# wolf_rev_d.net
KiCad netlist of a schematic drawn in EAGLE
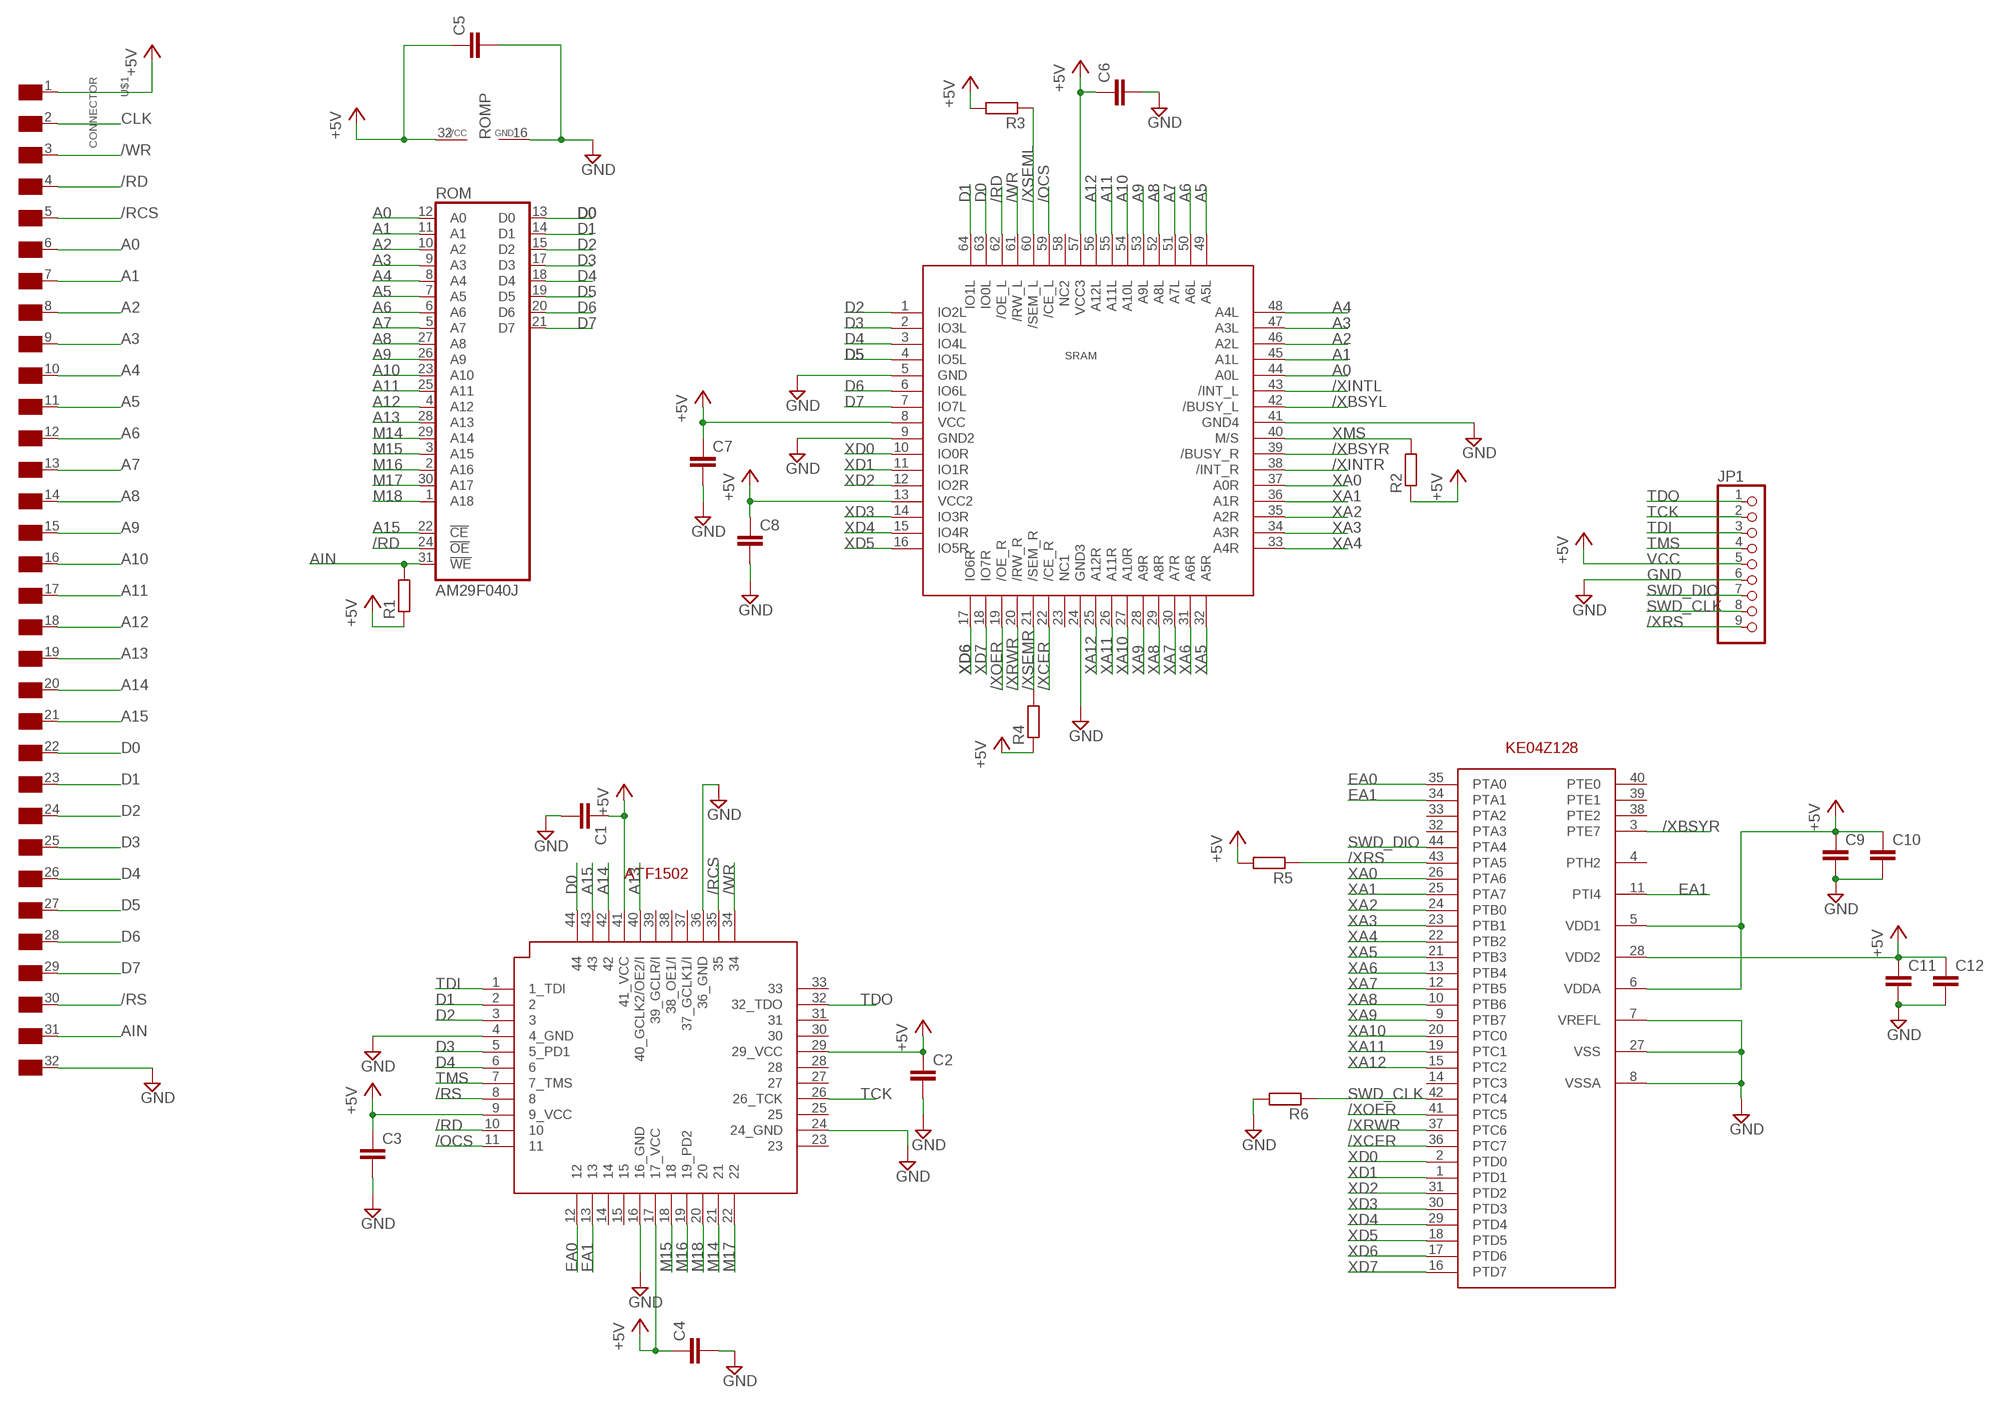
[diagram p0: schematic, sheet 1]

(export (version "E")
  (design (tool "Eeschema 10.0.6"))
  (components
    (comp (ref "ATF1502")
      (value "ATF1502")
      (footprint "eagle-import:TQFP44")
      (libsource (lib "eagle-import") (part "ATF1502"))
    )
    (comp (ref "C1")
      (value "C-EUC0805")
      (footprint "eagle-import:C0805")
      (libsource (lib "eagle-import") (part "C-EUC0805"))
    )
    (comp (ref "C2")
      (value "C-EUC0805")
      (footprint "eagle-import:C0805")
      (libsource (lib "eagle-import") (part "C-EUC0805"))
    )
    (comp (ref "C3")
      (value "C-EUC0805")
      (footprint "eagle-import:C0805")
      (libsource (lib "eagle-import") (part "C-EUC0805"))
    )
    (comp (ref "C4")
      (value "C-EUC0805")
      (footprint "eagle-import:C0805")
      (libsource (lib "eagle-import") (part "C-EUC0805"))
    )
    (comp (ref "C5")
      (value "C-EUC0805")
      (footprint "eagle-import:C0805")
      (libsource (lib "eagle-import") (part "C-EUC0805"))
    )
    (comp (ref "C6")
      (value "C-EUC0805")
      (footprint "eagle-import:C0805")
      (libsource (lib "eagle-import") (part "C-EUC0805"))
    )
    (comp (ref "C7")
      (value "C-EUC0805")
      (footprint "eagle-import:C0805")
      (libsource (lib "eagle-import") (part "C-EUC0805"))
    )
    (comp (ref "C8")
      (value "C-EUC0805")
      (footprint "eagle-import:C0805")
      (libsource (lib "eagle-import") (part "C-EUC0805"))
    )
    (comp (ref "C9")
      (value "C-EUC0805")
      (footprint "eagle-import:C0805")
      (libsource (lib "eagle-import") (part "C-EUC0805"))
    )
    (comp (ref "C10")
      (value "C-EUC0805")
      (footprint "eagle-import:C0805")
      (libsource (lib "eagle-import") (part "C-EUC0805"))
    )
    (comp (ref "C11")
      (value "C-EUC0805")
      (footprint "eagle-import:C0805")
      (libsource (lib "eagle-import") (part "C-EUC0805"))
    )
    (comp (ref "C12")
      (value "C-EUC0805")
      (footprint "eagle-import:C0805")
      (libsource (lib "eagle-import") (part "C-EUC0805"))
    )
    (comp (ref "JP1")
      (value "PINHD-1X9")
      (footprint "eagle-import:1X09")
      (libsource (lib "eagle-import") (part "PINHD-1X9"))
    )
    (comp (ref "KE04Z128")
      (value "KE04Z128")
      (footprint "eagle-import:TQFP44")
      (libsource (lib "eagle-import") (part "KE04Z128VLD4"))
    )
    (comp (ref "R1")
      (value "R-EU_R0805")
      (footprint "eagle-import:R0805")
      (libsource (lib "eagle-import") (part "R-EU_R0805"))
    )
    (comp (ref "R2")
      (value "R-EU_R0805")
      (footprint "eagle-import:R0805")
      (libsource (lib "eagle-import") (part "R-EU_R0805"))
    )
    (comp (ref "R3")
      (value "R-EU_R0805")
      (footprint "eagle-import:R0805")
      (libsource (lib "eagle-import") (part "R-EU_R0805"))
    )
    (comp (ref "R4")
      (value "R-EU_R0805")
      (footprint "eagle-import:R0805")
      (libsource (lib "eagle-import") (part "R-EU_R0805"))
    )
    (comp (ref "R5")
      (value "R-EU_R0805")
      (footprint "eagle-import:R0805")
      (libsource (lib "eagle-import") (part "R-EU_R0805"))
    )
    (comp (ref "R6")
      (value "R-EU_R0805")
      (footprint "eagle-import:R0805")
      (libsource (lib "eagle-import") (part "R-EU_R0805"))
    )
    (comp (ref "ROM")
      (value "AM29F040J")
      (footprint "eagle-import:PLCC32R")
      (libsource (lib "eagle-import") (part "AM29F040J"))
    )
    (comp (ref "SRAM")
      (value "CY7C144E")
      (footprint "eagle-import:TQFP64")
      (libsource (lib "eagle-import") (part "CY7C144E"))
    )
    (comp (ref "U$1")
      (value "CONNECTOR")
      (footprint "eagle-import:CONNECTOR")
      (libsource (lib "eagle-import") (part "CONNECTOR"))
    )
  )
  (nets
    (net (code "1") (name "+5V") (class "Default")
      (node (ref "ATF1502") (pin "17") (pinfunction "17_VCC_17") (pintype "bidirectional"))
      (node (ref "ATF1502") (pin "29") (pinfunction "29_VCC_29") (pintype "bidirectional"))
      (node (ref "ATF1502") (pin "41") (pinfunction "41_VCC_41") (pintype "bidirectional"))
      (node (ref "ATF1502") (pin "9") (pinfunction "9_VCC_9") (pintype "bidirectional"))
      (node (ref "C1") (pin "1") (pinfunction "1_1") (pintype "passive"))
      (node (ref "C10") (pin "1") (pinfunction "1_1") (pintype "passive"))
      (node (ref "C11") (pin "1") (pinfunction "1_1") (pintype "passive"))
      (node (ref "C12") (pin "1") (pinfunction "1_1") (pintype "passive"))
      (node (ref "C2") (pin "1") (pinfunction "1_1") (pintype "passive"))
      (node (ref "C3") (pin "1") (pinfunction "1_1") (pintype "passive"))
      (node (ref "C4") (pin "1") (pinfunction "1_1") (pintype "passive"))
      (node (ref "C5") (pin "1") (pinfunction "1_1") (pintype "passive"))
      (node (ref "C6") (pin "1") (pinfunction "1_1") (pintype "passive"))
      (node (ref "C7") (pin "1") (pinfunction "1_1") (pintype "passive"))
      (node (ref "C8") (pin "1") (pinfunction "1_1") (pintype "passive"))
      (node (ref "C9") (pin "1") (pinfunction "1_1") (pintype "passive"))
      (node (ref "JP1") (pin "5") (pinfunction "5_5") (pintype "passive"))
      (node (ref "KE04Z128") (pin "28") (pinfunction "VDD2_28") (pintype "bidirectional"))
      (node (ref "KE04Z128") (pin "5") (pinfunction "VDD1_5") (pintype "bidirectional"))
      (node (ref "KE04Z128") (pin "6") (pinfunction "VDDA_6") (pintype "bidirectional"))
      (node (ref "R1") (pin "1") (pinfunction "1_1") (pintype "passive"))
      (node (ref "R2") (pin "1") (pinfunction "1_1") (pintype "passive"))
      (node (ref "R3") (pin "2") (pinfunction "2_2") (pintype "passive"))
      (node (ref "R4") (pin "1") (pinfunction "1_1") (pintype "passive"))
      (node (ref "R5") (pin "2") (pinfunction "2_2") (pintype "passive"))
      (node (ref "ROM") (pin "32") (pinfunction "VCC_32") (pintype "power_in"))
      (node (ref "SRAM") (pin "13") (pinfunction "VCC2_13") (pintype "bidirectional"))
      (node (ref "SRAM") (pin "57") (pinfunction "VCC3_57") (pintype "bidirectional"))
      (node (ref "SRAM") (pin "8") (pinfunction "VCC_8") (pintype "bidirectional"))
      (node (ref "U$1") (pin "1") (pinfunction "VDD_1") (pintype "power_in"))
    )
    (net (code "2") (name "/A0") (class "Default")
      (node (ref "ROM") (pin "12") (pinfunction "A0_12") (pintype "input"))
      (node (ref "SRAM") (pin "44") (pinfunction "A0L_44") (pintype "bidirectional"))
      (node (ref "U$1") (pin "6") (pinfunction "A0_6") (pintype "bidirectional"))
    )
    (net (code "3") (name "/A1") (class "Default")
      (node (ref "ROM") (pin "11") (pinfunction "A1_11") (pintype "input"))
      (node (ref "SRAM") (pin "45") (pinfunction "A1L_45") (pintype "bidirectional"))
      (node (ref "U$1") (pin "7") (pinfunction "A1_7") (pintype "bidirectional"))
    )
    (net (code "4") (name "/A2") (class "Default")
      (node (ref "ROM") (pin "10") (pinfunction "A2_10") (pintype "input"))
      (node (ref "SRAM") (pin "46") (pinfunction "A2L_46") (pintype "bidirectional"))
      (node (ref "U$1") (pin "8") (pinfunction "A2_8") (pintype "bidirectional"))
    )
    (net (code "5") (name "/A3") (class "Default")
      (node (ref "ROM") (pin "9") (pinfunction "A3_9") (pintype "input"))
      (node (ref "SRAM") (pin "47") (pinfunction "A3L_47") (pintype "bidirectional"))
      (node (ref "U$1") (pin "9") (pinfunction "A3_9") (pintype "bidirectional"))
    )
    (net (code "6") (name "/A4") (class "Default")
      (node (ref "ROM") (pin "8") (pinfunction "A4_8") (pintype "input"))
      (node (ref "SRAM") (pin "48") (pinfunction "A4L_48") (pintype "bidirectional"))
      (node (ref "U$1") (pin "10") (pinfunction "A4_10") (pintype "bidirectional"))
    )
    (net (code "7") (name "/A5") (class "Default")
      (node (ref "ROM") (pin "7") (pinfunction "A5_7") (pintype "input"))
      (node (ref "SRAM") (pin "49") (pinfunction "A5L_49") (pintype "bidirectional"))
      (node (ref "U$1") (pin "11") (pinfunction "A5_11") (pintype "bidirectional"))
    )
    (net (code "8") (name "/A6") (class "Default")
      (node (ref "ROM") (pin "6") (pinfunction "A6_6") (pintype "input"))
      (node (ref "SRAM") (pin "50") (pinfunction "A6L_50") (pintype "bidirectional"))
      (node (ref "U$1") (pin "12") (pinfunction "A6_12") (pintype "bidirectional"))
    )
    (net (code "9") (name "/A7") (class "Default")
      (node (ref "ROM") (pin "5") (pinfunction "A7_5") (pintype "input"))
      (node (ref "SRAM") (pin "51") (pinfunction "A7L_51") (pintype "bidirectional"))
      (node (ref "U$1") (pin "13") (pinfunction "A7_13") (pintype "bidirectional"))
    )
    (net (code "10") (name "/A8") (class "Default")
      (node (ref "ROM") (pin "27") (pinfunction "A8_27") (pintype "input"))
      (node (ref "SRAM") (pin "52") (pinfunction "A8L_52") (pintype "bidirectional"))
      (node (ref "U$1") (pin "14") (pinfunction "A8_14") (pintype "bidirectional"))
    )
    (net (code "11") (name "/A9") (class "Default")
      (node (ref "ROM") (pin "26") (pinfunction "A9_26") (pintype "input"))
      (node (ref "SRAM") (pin "53") (pinfunction "A9L_53") (pintype "bidirectional"))
      (node (ref "U$1") (pin "15") (pinfunction "A9_15") (pintype "bidirectional"))
    )
    (net (code "12") (name "/A10") (class "Default")
      (node (ref "ROM") (pin "23") (pinfunction "A10_23") (pintype "input"))
      (node (ref "SRAM") (pin "54") (pinfunction "A10L_54") (pintype "bidirectional"))
      (node (ref "U$1") (pin "16") (pinfunction "A10_16") (pintype "bidirectional"))
    )
    (net (code "13") (name "/A11") (class "Default")
      (node (ref "ROM") (pin "25") (pinfunction "A11_25") (pintype "input"))
      (node (ref "SRAM") (pin "55") (pinfunction "A11L_55") (pintype "bidirectional"))
      (node (ref "U$1") (pin "17") (pinfunction "A11_17") (pintype "bidirectional"))
    )
    (net (code "14") (name "/A12") (class "Default")
      (node (ref "ROM") (pin "4") (pinfunction "A12_4") (pintype "input"))
      (node (ref "SRAM") (pin "56") (pinfunction "A12L_56") (pintype "bidirectional"))
      (node (ref "U$1") (pin "18") (pinfunction "A12_18") (pintype "bidirectional"))
    )
    (net (code "15") (name "/A13") (class "Default")
      (node (ref "ATF1502") (pin "40") (pinfunction "40_GCLK2/OE2/I_40") (pintype "bidirectional"))
      (node (ref "ROM") (pin "28") (pinfunction "A13_28") (pintype "input"))
      (node (ref "U$1") (pin "19") (pinfunction "A13_19") (pintype "bidirectional"))
    )
    (net (code "16") (name "/A14") (class "Default")
      (node (ref "ATF1502") (pin "42") (pinfunction "42_42") (pintype "bidirectional"))
      (node (ref "U$1") (pin "20") (pinfunction "A14_20") (pintype "bidirectional"))
    )
    (net (code "17") (name "/A15") (class "Default")
      (node (ref "ATF1502") (pin "43") (pinfunction "43_43") (pintype "bidirectional"))
      (node (ref "ROM") (pin "22") (pinfunction "~{CE}_22") (pintype "input"))
      (node (ref "U$1") (pin "21") (pinfunction "A15_21") (pintype "bidirectional"))
    )
    (net (code "18") (name "/AIN") (class "Default")
      (node (ref "R1") (pin "2") (pinfunction "2_2") (pintype "passive"))
      (node (ref "ROM") (pin "31") (pinfunction "~{WE}_31") (pintype "input"))
      (node (ref "U$1") (pin "31") (pinfunction "VIN_31") (pintype "bidirectional"))
    )
    (net (code "20") (name "/CLK") (class "Default")
      (node (ref "U$1") (pin "2") (pinfunction "NC_2") (pintype "no_connect"))
    )
    (net (code "21") (name "/D0") (class "Default")
      (node (ref "ATF1502") (pin "44") (pinfunction "44_44") (pintype "bidirectional"))
      (node (ref "ROM") (pin "13") (pinfunction "D0_13") (pintype "tri_state"))
      (node (ref "SRAM") (pin "63") (pinfunction "IO0L_63") (pintype "bidirectional"))
      (node (ref "U$1") (pin "22") (pinfunction "D0_22") (pintype "bidirectional"))
    )
    (net (code "22") (name "/D1") (class "Default")
      (node (ref "ATF1502") (pin "2") (pinfunction "2_2") (pintype "bidirectional"))
      (node (ref "ROM") (pin "14") (pinfunction "D1_14") (pintype "tri_state"))
      (node (ref "SRAM") (pin "64") (pinfunction "IO1L_64") (pintype "bidirectional"))
      (node (ref "U$1") (pin "23") (pinfunction "D1_23") (pintype "bidirectional"))
    )
    (net (code "23") (name "/D2") (class "Default")
      (node (ref "ATF1502") (pin "3") (pinfunction "3_3") (pintype "bidirectional"))
      (node (ref "ROM") (pin "15") (pinfunction "D2_15") (pintype "tri_state"))
      (node (ref "SRAM") (pin "1") (pinfunction "IO2L_1") (pintype "bidirectional"))
      (node (ref "U$1") (pin "24") (pinfunction "D2_24") (pintype "bidirectional"))
    )
    (net (code "24") (name "/D3") (class "Default")
      (node (ref "ATF1502") (pin "5") (pinfunction "5_PD1_5") (pintype "bidirectional"))
      (node (ref "ROM") (pin "17") (pinfunction "D3_17") (pintype "tri_state"))
      (node (ref "SRAM") (pin "2") (pinfunction "IO3L_2") (pintype "bidirectional"))
      (node (ref "U$1") (pin "25") (pinfunction "D3_25") (pintype "bidirectional"))
    )
    (net (code "25") (name "/D4") (class "Default")
      (node (ref "ATF1502") (pin "6") (pinfunction "6_6") (pintype "bidirectional"))
      (node (ref "ROM") (pin "18") (pinfunction "D4_18") (pintype "tri_state"))
      (node (ref "SRAM") (pin "3") (pinfunction "IO4L_3") (pintype "bidirectional"))
      (node (ref "U$1") (pin "26") (pinfunction "D4_26") (pintype "bidirectional"))
    )
    (net (code "26") (name "/D5") (class "Default")
      (node (ref "ROM") (pin "19") (pinfunction "D5_19") (pintype "tri_state"))
      (node (ref "SRAM") (pin "4") (pinfunction "IO5L_4") (pintype "bidirectional"))
      (node (ref "U$1") (pin "27") (pinfunction "D5_27") (pintype "bidirectional"))
    )
    (net (code "27") (name "/D6") (class "Default")
      (node (ref "ROM") (pin "20") (pinfunction "D6_20") (pintype "tri_state"))
      (node (ref "SRAM") (pin "6") (pinfunction "IO6L_6") (pintype "bidirectional"))
      (node (ref "U$1") (pin "28") (pinfunction "D6_28") (pintype "bidirectional"))
    )
    (net (code "28") (name "/D7") (class "Default")
      (node (ref "ROM") (pin "21") (pinfunction "D7_21") (pintype "tri_state"))
      (node (ref "SRAM") (pin "7") (pinfunction "IO7L_7") (pintype "bidirectional"))
      (node (ref "U$1") (pin "29") (pinfunction "D7_29") (pintype "bidirectional"))
    )
    (net (code "29") (name "/EA0") (class "Default")
      (node (ref "ATF1502") (pin "12") (pinfunction "12_12") (pintype "bidirectional"))
      (node (ref "KE04Z128") (pin "35") (pinfunction "PTA0_35") (pintype "bidirectional"))
    )
    (net (code "30") (name "/EA1") (class "Default")
      (node (ref "ATF1502") (pin "13") (pinfunction "13_13") (pintype "bidirectional"))
      (node (ref "KE04Z128") (pin "11") (pinfunction "PTI4_11") (pintype "bidirectional"))
      (node (ref "KE04Z128") (pin "34") (pinfunction "PTA1_34") (pintype "bidirectional"))
    )
    (net (code "31") (name "/M14") (class "Default")
      (node (ref "ATF1502") (pin "21") (pinfunction "21_21") (pintype "bidirectional"))
      (node (ref "ROM") (pin "29") (pinfunction "A14_29") (pintype "input"))
    )
    (net (code "32") (name "/M15") (class "Default")
      (node (ref "ATF1502") (pin "18") (pinfunction "18_18") (pintype "bidirectional"))
      (node (ref "ROM") (pin "3") (pinfunction "A15_3") (pintype "input"))
    )
    (net (code "33") (name "/M16") (class "Default")
      (node (ref "ATF1502") (pin "19") (pinfunction "19_PD2_19") (pintype "bidirectional"))
      (node (ref "ROM") (pin "2") (pinfunction "A16_2") (pintype "input"))
    )
    (net (code "34") (name "/M17") (class "Default")
      (node (ref "ATF1502") (pin "22") (pinfunction "22_22") (pintype "bidirectional"))
      (node (ref "ROM") (pin "30") (pinfunction "A17_30") (pintype "input"))
    )
    (net (code "35") (name "/M18") (class "Default")
      (node (ref "ATF1502") (pin "20") (pinfunction "20_20") (pintype "bidirectional"))
      (node (ref "ROM") (pin "1") (pinfunction "A18_1") (pintype "input"))
    )
    (net (code "36") (name "/SWD_CLK") (class "Default")
      (node (ref "JP1") (pin "8") (pinfunction "8_8") (pintype "passive"))
      (node (ref "KE04Z128") (pin "42") (pinfunction "PTC4_42") (pintype "bidirectional"))
      (node (ref "R6") (pin "1") (pinfunction "1_1") (pintype "passive"))
    )
    (net (code "37") (name "/SWD_DIO") (class "Default")
      (node (ref "JP1") (pin "7") (pinfunction "7_7") (pintype "passive"))
      (node (ref "KE04Z128") (pin "44") (pinfunction "PTA4_44") (pintype "bidirectional"))
    )
    (net (code "38") (name "/TCK") (class "Default")
      (node (ref "ATF1502") (pin "26") (pinfunction "26_TCK_26") (pintype "bidirectional"))
      (node (ref "JP1") (pin "2") (pinfunction "2_2") (pintype "passive"))
    )
    (net (code "39") (name "/TDI") (class "Default")
      (node (ref "ATF1502") (pin "1") (pinfunction "1_TDI_1") (pintype "bidirectional"))
      (node (ref "JP1") (pin "3") (pinfunction "3_3") (pintype "passive"))
    )
    (net (code "40") (name "/TDO") (class "Default")
      (node (ref "ATF1502") (pin "32") (pinfunction "32_TDO_32") (pintype "bidirectional"))
      (node (ref "JP1") (pin "1") (pinfunction "1_1") (pintype "passive"))
    )
    (net (code "41") (name "/TMS") (class "Default")
      (node (ref "ATF1502") (pin "7") (pinfunction "7_TMS_7") (pintype "bidirectional"))
      (node (ref "JP1") (pin "4") (pinfunction "4_4") (pintype "passive"))
    )
    (net (code "42") (name "/XA0") (class "Default")
      (node (ref "KE04Z128") (pin "26") (pinfunction "PTA6_26") (pintype "bidirectional"))
      (node (ref "SRAM") (pin "37") (pinfunction "A0R_37") (pintype "bidirectional"))
    )
    (net (code "43") (name "/XA1") (class "Default")
      (node (ref "KE04Z128") (pin "25") (pinfunction "PTA7_25") (pintype "bidirectional"))
      (node (ref "SRAM") (pin "36") (pinfunction "A1R_36") (pintype "bidirectional"))
    )
    (net (code "44") (name "/XA2") (class "Default")
      (node (ref "KE04Z128") (pin "24") (pinfunction "PTB0_24") (pintype "bidirectional"))
      (node (ref "SRAM") (pin "35") (pinfunction "A2R_35") (pintype "bidirectional"))
    )
    (net (code "45") (name "/XA3") (class "Default")
      (node (ref "KE04Z128") (pin "23") (pinfunction "PTB1_23") (pintype "bidirectional"))
      (node (ref "SRAM") (pin "34") (pinfunction "A3R_34") (pintype "bidirectional"))
    )
    (net (code "46") (name "/XA4") (class "Default")
      (node (ref "KE04Z128") (pin "22") (pinfunction "PTB2_22") (pintype "bidirectional"))
      (node (ref "SRAM") (pin "33") (pinfunction "A4R_33") (pintype "bidirectional"))
    )
    (net (code "47") (name "/XA5") (class "Default")
      (node (ref "KE04Z128") (pin "21") (pinfunction "PTB3_21") (pintype "bidirectional"))
      (node (ref "SRAM") (pin "32") (pinfunction "A5R_32") (pintype "bidirectional"))
    )
    (net (code "48") (name "/XA6") (class "Default")
      (node (ref "KE04Z128") (pin "13") (pinfunction "PTB4_13") (pintype "bidirectional"))
      (node (ref "SRAM") (pin "31") (pinfunction "A6R_31") (pintype "bidirectional"))
    )
    (net (code "49") (name "/XA7") (class "Default")
      (node (ref "KE04Z128") (pin "12") (pinfunction "PTB5_12") (pintype "bidirectional"))
      (node (ref "SRAM") (pin "30") (pinfunction "A7R_30") (pintype "bidirectional"))
    )
    (net (code "50") (name "/XA8") (class "Default")
      (node (ref "KE04Z128") (pin "10") (pinfunction "PTB6_10") (pintype "bidirectional"))
      (node (ref "SRAM") (pin "29") (pinfunction "A8R_29") (pintype "bidirectional"))
    )
    (net (code "51") (name "/XA9") (class "Default")
      (node (ref "KE04Z128") (pin "9") (pinfunction "PTB7_9") (pintype "bidirectional"))
      (node (ref "SRAM") (pin "28") (pinfunction "A9R_28") (pintype "bidirectional"))
    )
    (net (code "52") (name "/XA10") (class "Default")
      (node (ref "KE04Z128") (pin "20") (pinfunction "PTC0_20") (pintype "bidirectional"))
      (node (ref "SRAM") (pin "27") (pinfunction "A10R_27") (pintype "bidirectional"))
    )
    (net (code "53") (name "/XA11") (class "Default")
      (node (ref "KE04Z128") (pin "19") (pinfunction "PTC1_19") (pintype "bidirectional"))
      (node (ref "SRAM") (pin "26") (pinfunction "A11R_26") (pintype "bidirectional"))
    )
    (net (code "54") (name "/XA12") (class "Default")
      (node (ref "KE04Z128") (pin "15") (pinfunction "PTC2_15") (pintype "bidirectional"))
      (node (ref "SRAM") (pin "25") (pinfunction "A12R_25") (pintype "bidirectional"))
    )
    (net (code "55") (name "/XD0") (class "Default")
      (node (ref "KE04Z128") (pin "2") (pinfunction "PTD0_2") (pintype "bidirectional"))
      (node (ref "SRAM") (pin "10") (pinfunction "IO0R_10") (pintype "bidirectional"))
    )
    (net (code "56") (name "/XD1") (class "Default")
      (node (ref "KE04Z128") (pin "1") (pinfunction "PTD1_1") (pintype "bidirectional"))
      (node (ref "SRAM") (pin "11") (pinfunction "IO1R_11") (pintype "bidirectional"))
    )
    (net (code "57") (name "/XD2") (class "Default")
      (node (ref "KE04Z128") (pin "31") (pinfunction "PTD2_31") (pintype "bidirectional"))
      (node (ref "SRAM") (pin "12") (pinfunction "IO2R_12") (pintype "bidirectional"))
    )
    (net (code "58") (name "/XD3") (class "Default")
      (node (ref "KE04Z128") (pin "30") (pinfunction "PTD3_30") (pintype "bidirectional"))
      (node (ref "SRAM") (pin "14") (pinfunction "IO3R_14") (pintype "bidirectional"))
    )
    (net (code "59") (name "/XD4") (class "Default")
      (node (ref "KE04Z128") (pin "29") (pinfunction "PTD4_29") (pintype "bidirectional"))
      (node (ref "SRAM") (pin "15") (pinfunction "IO4R_15") (pintype "bidirectional"))
    )
    (net (code "60") (name "/XD5") (class "Default")
      (node (ref "KE04Z128") (pin "18") (pinfunction "PTD5_18") (pintype "bidirectional"))
      (node (ref "SRAM") (pin "16") (pinfunction "IO5R_16") (pintype "bidirectional"))
    )
    (net (code "61") (name "/XD6") (class "Default")
      (node (ref "KE04Z128") (pin "17") (pinfunction "PTD6_17") (pintype "bidirectional"))
      (node (ref "SRAM") (pin "17") (pinfunction "IO6R_17") (pintype "bidirectional"))
    )
    (net (code "62") (name "/XD7") (class "Default")
      (node (ref "KE04Z128") (pin "16") (pinfunction "PTD7_16") (pintype "bidirectional"))
      (node (ref "SRAM") (pin "18") (pinfunction "IO7R_18") (pintype "bidirectional"))
    )
    (net (code "63") (name "/XMS") (class "Default")
      (node (ref "R2") (pin "2") (pinfunction "2_2") (pintype "passive"))
      (node (ref "SRAM") (pin "40") (pinfunction "M/S_40") (pintype "bidirectional"))
    )
    (net (code "64") (name "/{slash}OCS") (class "Default")
      (node (ref "ATF1502") (pin "11") (pinfunction "11_11") (pintype "bidirectional"))
      (node (ref "SRAM") (pin "59") (pinfunction "/CE_L_59") (pintype "bidirectional"))
    )
    (net (code "65") (name "/{slash}RCS") (class "Default")
      (node (ref "ATF1502") (pin "35") (pinfunction "35_35") (pintype "bidirectional"))
      (node (ref "U$1") (pin "5") (pinfunction "/RCS_5") (pintype "bidirectional"))
    )
    (net (code "66") (name "/{slash}RD") (class "Default")
      (node (ref "ATF1502") (pin "10") (pinfunction "10_10") (pintype "bidirectional"))
      (node (ref "ROM") (pin "24") (pinfunction "~{OE}_24") (pintype "input"))
      (node (ref "SRAM") (pin "62") (pinfunction "/OE_L_62") (pintype "bidirectional"))
      (node (ref "U$1") (pin "4") (pinfunction "/RD_4") (pintype "bidirectional"))
    )
    (net (code "67") (name "/{slash}RS") (class "Default")
      (node (ref "ATF1502") (pin "8") (pinfunction "8_8") (pintype "bidirectional"))
      (node (ref "U$1") (pin "30") (pinfunction "/RS_30") (pintype "bidirectional"))
    )
    (net (code "68") (name "/{slash}WR") (class "Default")
      (node (ref "ATF1502") (pin "34") (pinfunction "34_34") (pintype "bidirectional"))
      (node (ref "SRAM") (pin "61") (pinfunction "/RW_L_61") (pintype "bidirectional"))
      (node (ref "U$1") (pin "3") (pinfunction "/WR_3") (pintype "bidirectional"))
    )
    (net (code "69") (name "/{slash}XBSYL") (class "Default")
      (node (ref "SRAM") (pin "42") (pinfunction "/BUSY_L_42") (pintype "bidirectional"))
    )
    (net (code "70") (name "/{slash}XBSYR") (class "Default")
      (node (ref "KE04Z128") (pin "3") (pinfunction "PTE7_3") (pintype "bidirectional"))
      (node (ref "SRAM") (pin "39") (pinfunction "/BUSY_R_39") (pintype "bidirectional"))
    )
    (net (code "71") (name "/{slash}XCER") (class "Default")
      (node (ref "KE04Z128") (pin "36") (pinfunction "PTC7_36") (pintype "bidirectional"))
      (node (ref "SRAM") (pin "22") (pinfunction "/CE_R_22") (pintype "bidirectional"))
    )
    (net (code "72") (name "/{slash}XINTL") (class "Default")
      (node (ref "SRAM") (pin "43") (pinfunction "/INT_L_43") (pintype "bidirectional"))
    )
    (net (code "73") (name "/{slash}XINTR") (class "Default")
      (node (ref "SRAM") (pin "38") (pinfunction "/INT_R_38") (pintype "bidirectional"))
    )
    (net (code "74") (name "/{slash}XOER") (class "Default")
      (node (ref "KE04Z128") (pin "41") (pinfunction "PTC5_41") (pintype "bidirectional"))
      (node (ref "SRAM") (pin "19") (pinfunction "/OE_R_19") (pintype "bidirectional"))
    )
    (net (code "75") (name "/{slash}XRS") (class "Default")
      (node (ref "JP1") (pin "9") (pinfunction "9_9") (pintype "passive"))
      (node (ref "KE04Z128") (pin "43") (pinfunction "PTA5_43") (pintype "bidirectional"))
      (node (ref "R5") (pin "1") (pinfunction "1_1") (pintype "passive"))
    )
    (net (code "76") (name "/{slash}XRWR") (class "Default")
      (node (ref "KE04Z128") (pin "37") (pinfunction "PTC6_37") (pintype "bidirectional"))
      (node (ref "SRAM") (pin "20") (pinfunction "/RW_R_20") (pintype "bidirectional"))
    )
    (net (code "77") (name "/{slash}XSEML") (class "Default")
      (node (ref "R3") (pin "1") (pinfunction "1_1") (pintype "passive"))
      (node (ref "SRAM") (pin "60") (pinfunction "/SEM_L_60") (pintype "bidirectional"))
    )
    (net (code "78") (name "/{slash}XSEMR") (class "Default")
      (node (ref "R4") (pin "2") (pinfunction "2_2") (pintype "passive"))
      (node (ref "SRAM") (pin "21") (pinfunction "/SEM_R_21") (pintype "bidirectional"))
    )
    (net (code "79") (name "GND") (class "Default")
      (node (ref "ATF1502") (pin "16") (pinfunction "16_GND_16") (pintype "bidirectional"))
      (node (ref "ATF1502") (pin "24") (pinfunction "24_GND_24") (pintype "bidirectional"))
      (node (ref "ATF1502") (pin "36") (pinfunction "36_GND_36") (pintype "bidirectional"))
      (node (ref "ATF1502") (pin "4") (pinfunction "4_GND_4") (pintype "bidirectional"))
      (node (ref "C1") (pin "2") (pinfunction "2_2") (pintype "passive"))
      (node (ref "C10") (pin "2") (pinfunction "2_2") (pintype "passive"))
      (node (ref "C11") (pin "2") (pinfunction "2_2") (pintype "passive"))
      (node (ref "C12") (pin "2") (pinfunction "2_2") (pintype "passive"))
      (node (ref "C2") (pin "2") (pinfunction "2_2") (pintype "passive"))
      (node (ref "C3") (pin "2") (pinfunction "2_2") (pintype "passive"))
      (node (ref "C4") (pin "2") (pinfunction "2_2") (pintype "passive"))
      (node (ref "C5") (pin "2") (pinfunction "2_2") (pintype "passive"))
      (node (ref "C6") (pin "2") (pinfunction "2_2") (pintype "passive"))
      (node (ref "C7") (pin "2") (pinfunction "2_2") (pintype "passive"))
      (node (ref "C8") (pin "2") (pinfunction "2_2") (pintype "passive"))
      (node (ref "C9") (pin "2") (pinfunction "2_2") (pintype "passive"))
      (node (ref "JP1") (pin "6") (pinfunction "6_6") (pintype "passive"))
      (node (ref "KE04Z128") (pin "27") (pinfunction "VSS_27") (pintype "bidirectional"))
      (node (ref "KE04Z128") (pin "7") (pinfunction "VREFL_7") (pintype "bidirectional"))
      (node (ref "KE04Z128") (pin "8") (pinfunction "VSSA_8") (pintype "bidirectional"))
      (node (ref "R6") (pin "2") (pinfunction "2_2") (pintype "passive"))
      (node (ref "ROM") (pin "16") (pinfunction "GND_16") (pintype "power_in"))
      (node (ref "SRAM") (pin "24") (pinfunction "GND3_24") (pintype "bidirectional"))
      (node (ref "SRAM") (pin "41") (pinfunction "GND4_41") (pintype "bidirectional"))
      (node (ref "SRAM") (pin "5") (pinfunction "GND_5") (pintype "bidirectional"))
      (node (ref "SRAM") (pin "9") (pinfunction "GND2_9") (pintype "bidirectional"))
      (node (ref "U$1") (pin "32") (pinfunction "GND_32") (pintype "power_in"))
    )
    (net (code "80") (name "unconnected-(ATF1502-37_GCLK1{slash}I-Pad37)") (class "Default")
      (node (ref "ATF1502") (pin "37") (pinfunction "37_GCLK1/I_37") (pintype "bidirectional"))
    )
    (net (code "81") (name "unconnected-(ATF1502-38_OE1{slash}I-Pad38)") (class "Default")
      (node (ref "ATF1502") (pin "38") (pinfunction "38_OE1/I_38") (pintype "bidirectional"))
    )
    (net (code "82") (name "unconnected-(ATF1502-39_GCLR{slash}I-Pad39)") (class "Default")
      (node (ref "ATF1502") (pin "39") (pinfunction "39_GCLR/I_39") (pintype "bidirectional"))
    )
    (net (code "83") (name "unconnected-(ATF1502-Pad14)") (class "Default")
      (node (ref "ATF1502") (pin "14") (pinfunction "14_14") (pintype "bidirectional"))
    )
    (net (code "84") (name "unconnected-(ATF1502-Pad15)") (class "Default")
      (node (ref "ATF1502") (pin "15") (pinfunction "15_15") (pintype "bidirectional"))
    )
    (net (code "85") (name "unconnected-(ATF1502-Pad23)") (class "Default")
      (node (ref "ATF1502") (pin "23") (pinfunction "23_23") (pintype "bidirectional"))
    )
    (net (code "86") (name "unconnected-(ATF1502-Pad25)") (class "Default")
      (node (ref "ATF1502") (pin "25") (pinfunction "25_25") (pintype "bidirectional"))
    )
    (net (code "87") (name "unconnected-(ATF1502-Pad27)") (class "Default")
      (node (ref "ATF1502") (pin "27") (pinfunction "27_27") (pintype "bidirectional"))
    )
    (net (code "88") (name "unconnected-(ATF1502-Pad28)") (class "Default")
      (node (ref "ATF1502") (pin "28") (pinfunction "28_28") (pintype "bidirectional"))
    )
    (net (code "89") (name "unconnected-(ATF1502-Pad30)") (class "Default")
      (node (ref "ATF1502") (pin "30") (pinfunction "30_30") (pintype "bidirectional"))
    )
    (net (code "90") (name "unconnected-(ATF1502-Pad31)") (class "Default")
      (node (ref "ATF1502") (pin "31") (pinfunction "31_31") (pintype "bidirectional"))
    )
    (net (code "91") (name "unconnected-(ATF1502-Pad33)") (class "Default")
      (node (ref "ATF1502") (pin "33") (pinfunction "33_33") (pintype "bidirectional"))
    )
    (net (code "92") (name "unconnected-(KE04Z128-PTA2-Pad33)") (class "Default")
      (node (ref "KE04Z128") (pin "33") (pinfunction "PTA2_33") (pintype "bidirectional"))
    )
    (net (code "93") (name "unconnected-(KE04Z128-PTA3-Pad32)") (class "Default")
      (node (ref "KE04Z128") (pin "32") (pinfunction "PTA3_32") (pintype "bidirectional"))
    )
    (net (code "94") (name "unconnected-(KE04Z128-PTC3-Pad14)") (class "Default")
      (node (ref "KE04Z128") (pin "14") (pinfunction "PTC3_14") (pintype "bidirectional"))
    )
    (net (code "95") (name "unconnected-(KE04Z128-PTE0-Pad40)") (class "Default")
      (node (ref "KE04Z128") (pin "40") (pinfunction "PTE0_40") (pintype "bidirectional"))
    )
    (net (code "96") (name "unconnected-(KE04Z128-PTE1-Pad39)") (class "Default")
      (node (ref "KE04Z128") (pin "39") (pinfunction "PTE1_39") (pintype "bidirectional"))
    )
    (net (code "97") (name "unconnected-(KE04Z128-PTE2-Pad38)") (class "Default")
      (node (ref "KE04Z128") (pin "38") (pinfunction "PTE2_38") (pintype "bidirectional"))
    )
    (net (code "98") (name "unconnected-(KE04Z128-PTH2-Pad4)") (class "Default")
      (node (ref "KE04Z128") (pin "4") (pinfunction "PTH2_4") (pintype "bidirectional"))
    )
    (net (code "99") (name "unconnected-(SRAM-NC1-Pad23)") (class "Default")
      (node (ref "SRAM") (pin "23") (pinfunction "NC1_23") (pintype "bidirectional"))
    )
    (net (code "100") (name "unconnected-(SRAM-NC2-Pad58)") (class "Default")
      (node (ref "SRAM") (pin "58") (pinfunction "NC2_58") (pintype "bidirectional"))
    )
  )
)
